# ECG_V3.net
KiCad netlist of a schematic drawn in EAGLE
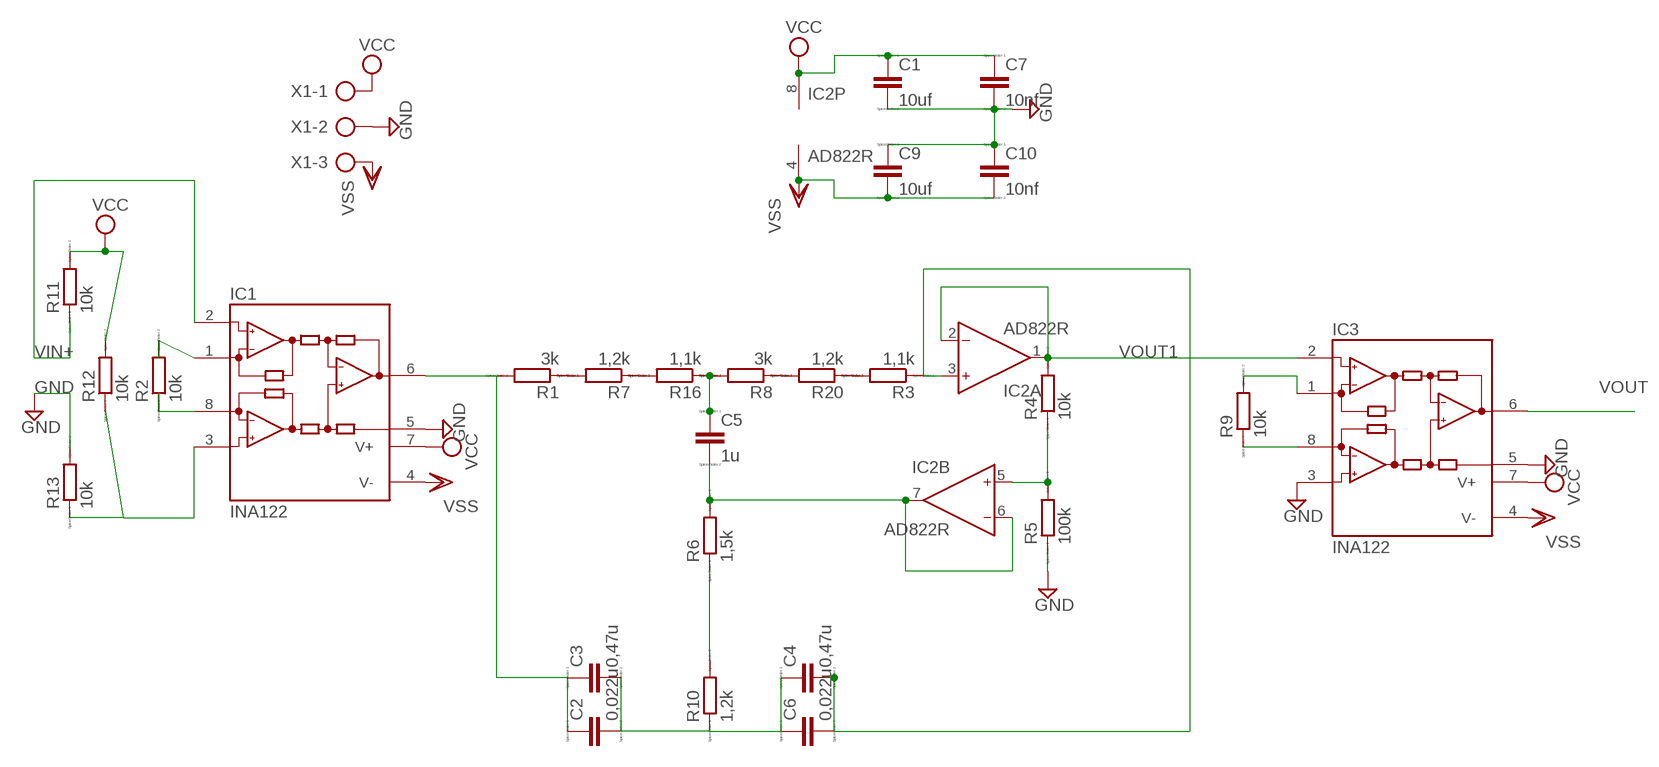
[diagram p0: schematic, sheet 1]

(export (version "E")
  (design (tool "Eeschema 10.0.6"))
  (components
    (comp (ref "C1")
      (value "10uf")
      (footprint "eagle-import:C0603")
      (libsource (lib "eagle-import") (part "CC0603"))
    )
    (comp (ref "C2")
      (value "0,022u")
      (footprint "eagle-import:C0603")
      (libsource (lib "eagle-import") (part "CC0603"))
    )
    (comp (ref "C3")
      (value "0,47u")
      (footprint "eagle-import:C0603")
      (libsource (lib "eagle-import") (part "CC0603"))
    )
    (comp (ref "C4")
      (value "0,47u")
      (footprint "eagle-import:C0603")
      (libsource (lib "eagle-import") (part "CC0603"))
    )
    (comp (ref "C5")
      (value "1u")
      (footprint "eagle-import:C0603")
      (libsource (lib "eagle-import") (part "CC0603"))
    )
    (comp (ref "C6")
      (value "0,022u")
      (footprint "eagle-import:C0603")
      (libsource (lib "eagle-import") (part "CC0603"))
    )
    (comp (ref "C7")
      (value "10nf")
      (footprint "eagle-import:C0603")
      (libsource (lib "eagle-import") (part "CC0603"))
    )
    (comp (ref "C9")
      (value "10uf")
      (footprint "eagle-import:C0603")
      (libsource (lib "eagle-import") (part "CC0603"))
    )
    (comp (ref "C10")
      (value "10nf")
      (footprint "eagle-import:C0603")
      (libsource (lib "eagle-import") (part "CC0603"))
    )
    (comp (ref "IC1")
      (value "INA122")
      (footprint "eagle-import:SO08")
      (fields (field (name "MF") "TEXAS INSTRUMENTS") (field (name "MPN") "INA118U"))
      (libsource (lib "eagle-import") (part "INA118U"))
    )
    (comp (ref "IC2")
      (value "AD822R")
      (footprint "eagle-import:SO8")
      (fields (field (name "MF") "ANALOG DEVICES") (field (name "MPN") "AD822BRZ"))
      (libsource (lib "eagle-import") (part "AD822R"))
    )
    (comp (ref "IC3")
      (value "INA122")
      (footprint "eagle-import:SO08")
      (fields (field (name "MF") "TEXAS INSTRUMENTS") (field (name "MPN") "INA118U"))
      (libsource (lib "eagle-import") (part "INA118U"))
    )
    (comp (ref "R1")
      (value "3k")
      (footprint "eagle-import:R0603")
      (libsource (lib "eagle-import") (part "RR0603"))
    )
    (comp (ref "R2")
      (value "10k")
      (footprint "eagle-import:R0603")
      (libsource (lib "eagle-import") (part "RR0603"))
    )
    (comp (ref "R3")
      (value "1,1k")
      (footprint "eagle-import:R0603")
      (libsource (lib "eagle-import") (part "RR0603"))
    )
    (comp (ref "R4")
      (value "10k")
      (footprint "eagle-import:R0603")
      (libsource (lib "eagle-import") (part "RR0603"))
    )
    (comp (ref "R5")
      (value "100k")
      (footprint "eagle-import:R0603")
      (libsource (lib "eagle-import") (part "RR0603"))
    )
    (comp (ref "R6")
      (value "1,5k")
      (footprint "eagle-import:R0603")
      (libsource (lib "eagle-import") (part "RR0603"))
    )
    (comp (ref "R7")
      (value "1,2k")
      (footprint "eagle-import:R0603")
      (libsource (lib "eagle-import") (part "RR0603"))
    )
    (comp (ref "R8")
      (value "3k")
      (footprint "eagle-import:R0603")
      (libsource (lib "eagle-import") (part "RR0603"))
    )
    (comp (ref "R9")
      (value "10k")
      (footprint "eagle-import:R0603")
      (libsource (lib "eagle-import") (part "RR0603"))
    )
    (comp (ref "R10")
      (value "1,2k")
      (footprint "eagle-import:R0603")
      (libsource (lib "eagle-import") (part "RR0603"))
    )
    (comp (ref "R11")
      (value "10k")
      (footprint "eagle-import:R0603")
      (libsource (lib "eagle-import") (part "RR0603"))
    )
    (comp (ref "R12")
      (value "10k")
      (footprint "eagle-import:R0603")
      (libsource (lib "eagle-import") (part "RR0603"))
    )
    (comp (ref "R13")
      (value "10k")
      (footprint "eagle-import:R0603")
      (libsource (lib "eagle-import") (part "RR0603"))
    )
    (comp (ref "R16")
      (value "1,1k")
      (footprint "eagle-import:R0603")
      (libsource (lib "eagle-import") (part "RR0603"))
    )
    (comp (ref "R20")
      (value "1,2k")
      (footprint "eagle-import:R0603")
      (libsource (lib "eagle-import") (part "RR0603"))
    )
    (comp (ref "X1")
      (value "AK300/3")
      (footprint "eagle-import:AK300_3")
      (libsource (lib "eagle-import") (part "AK300/3"))
    )
  )
  (nets
    (net (code "1") (name "/VIN+") (class "Default")
      (node (ref "IC1") (pin "2") (pinfunction "-IN_2") (pintype "input"))
      (node (ref "R11") (pin "1") (pinfunction "1_1") (pintype "passive"))
    )
    (net (code "2") (name "/VOUT") (class "Default")
      (node (ref "IC3") (pin "6") (pinfunction "OUT_6") (pintype "output"))
    )
    (net (code "3") (name "/VOUT1") (class "Default")
      (node (ref "IC2") (pin "1") (pinfunction "OUT_1") (pintype "output"))
      (node (ref "IC2") (pin "2") (pinfunction "IN-_2") (pintype "input"))
      (node (ref "IC3") (pin "2") (pinfunction "-IN_2") (pintype "input"))
      (node (ref "R4") (pin "2") (pinfunction "2_2") (pintype "passive"))
    )
    (net (code "4") (name "GND") (class "Default")
      (node (ref "C1") (pin "2") (pinfunction "2_2") (pintype "passive"))
      (node (ref "C10") (pin "1") (pinfunction "1_1") (pintype "passive"))
      (node (ref "C7") (pin "2") (pinfunction "2_2") (pintype "passive"))
      (node (ref "C9") (pin "1") (pinfunction "1_1") (pintype "passive"))
      (node (ref "IC1") (pin "5") (pinfunction "REF_5") (pintype "passive"))
      (node (ref "IC3") (pin "3") (pinfunction "+IN_3") (pintype "input"))
      (node (ref "IC3") (pin "5") (pinfunction "REF_5") (pintype "passive"))
      (node (ref "R13") (pin "2") (pinfunction "2_2") (pintype "passive"))
      (node (ref "R5") (pin "1") (pinfunction "1_1") (pintype "passive"))
      (node (ref "X1") (pin "2") (pinfunction "KL_2") (pintype "passive"))
    )
    (net (code "5") (name "Net-(C2-Pad2)") (class "Default")
      (node (ref "C2") (pin "2") (pinfunction "2_2") (pintype "passive"))
      (node (ref "C3") (pin "2") (pinfunction "2_2") (pintype "passive"))
      (node (ref "C4") (pin "1") (pinfunction "1_1") (pintype "passive"))
      (node (ref "C6") (pin "1") (pinfunction "1_1") (pintype "passive"))
      (node (ref "R10") (pin "1") (pinfunction "1_1") (pintype "passive"))
    )
    (net (code "6") (name "Net-(C5-Pad1)") (class "Default")
      (node (ref "C5") (pin "1") (pinfunction "1_1") (pintype "passive"))
      (node (ref "R16") (pin "1") (pinfunction "1_1") (pintype "passive"))
      (node (ref "R8") (pin "2") (pinfunction "2_2") (pintype "passive"))
    )
    (net (code "7") (name "Net-(IC1-+IN)") (class "Default")
      (node (ref "IC1") (pin "3") (pinfunction "+IN_3") (pintype "input"))
      (node (ref "R12") (pin "1") (pinfunction "1_1") (pintype "passive"))
      (node (ref "R13") (pin "1") (pinfunction "1_1") (pintype "passive"))
    )
    (net (code "8") (name "Net-(IC1-OUT)") (class "Default")
      (node (ref "C2") (pin "1") (pinfunction "1_1") (pintype "passive"))
      (node (ref "C3") (pin "1") (pinfunction "1_1") (pintype "passive"))
      (node (ref "IC1") (pin "6") (pinfunction "OUT_6") (pintype "output"))
      (node (ref "R1") (pin "2") (pinfunction "2_2") (pintype "passive"))
    )
    (net (code "9") (name "Net-(IC1-RG-Pad1)") (class "Default")
      (node (ref "IC1") (pin "1") (pinfunction "RG_1") (pintype "passive"))
      (node (ref "R2") (pin "2") (pinfunction "2_2") (pintype "passive"))
    )
    (net (code "10") (name "Net-(IC1-RG-Pad8)") (class "Default")
      (node (ref "IC1") (pin "8") (pinfunction "RG_8") (pintype "passive"))
      (node (ref "R2") (pin "1") (pinfunction "1_1") (pintype "passive"))
    )
    (net (code "11") (name "Net-(IC2A-IN+)") (class "Default")
      (node (ref "C4") (pin "2") (pinfunction "2_2") (pintype "passive"))
      (node (ref "C6") (pin "2") (pinfunction "2_2") (pintype "passive"))
      (node (ref "IC2") (pin "3") (pinfunction "IN+_3") (pintype "input"))
      (node (ref "R3") (pin "1") (pinfunction "1_1") (pintype "passive"))
    )
    (net (code "12") (name "Net-(IC2B-IN+)") (class "Default")
      (node (ref "IC2") (pin "5") (pinfunction "IN+_5") (pintype "input"))
      (node (ref "R4") (pin "1") (pinfunction "1_1") (pintype "passive"))
      (node (ref "R5") (pin "2") (pinfunction "2_2") (pintype "passive"))
    )
    (net (code "13") (name "Net-(IC2B-IN-)") (class "Default")
      (node (ref "C5") (pin "2") (pinfunction "2_2") (pintype "passive"))
      (node (ref "IC2") (pin "6") (pinfunction "IN-_6") (pintype "input"))
      (node (ref "IC2") (pin "7") (pinfunction "OUT_7") (pintype "output"))
      (node (ref "R6") (pin "2") (pinfunction "2_2") (pintype "passive"))
    )
    (net (code "14") (name "Net-(IC3-RG-Pad1)") (class "Default")
      (node (ref "IC3") (pin "1") (pinfunction "RG_1") (pintype "passive"))
      (node (ref "R9") (pin "2") (pinfunction "2_2") (pintype "passive"))
    )
    (net (code "15") (name "Net-(IC3-RG-Pad8)") (class "Default")
      (node (ref "IC3") (pin "8") (pinfunction "RG_8") (pintype "passive"))
      (node (ref "R9") (pin "1") (pinfunction "1_1") (pintype "passive"))
    )
    (net (code "16") (name "Net-(R1-Pad1)") (class "Default")
      (node (ref "R1") (pin "1") (pinfunction "1_1") (pintype "passive"))
      (node (ref "R7") (pin "2") (pinfunction "2_2") (pintype "passive"))
    )
    (net (code "17") (name "Net-(R10-Pad2)") (class "Default")
      (node (ref "R10") (pin "2") (pinfunction "2_2") (pintype "passive"))
      (node (ref "R6") (pin "1") (pinfunction "1_1") (pintype "passive"))
    )
    (net (code "18") (name "Net-(R16-Pad2)") (class "Default")
      (node (ref "R16") (pin "2") (pinfunction "2_2") (pintype "passive"))
      (node (ref "R7") (pin "1") (pinfunction "1_1") (pintype "passive"))
    )
    (net (code "19") (name "Net-(R20-Pad1)") (class "Default")
      (node (ref "R20") (pin "1") (pinfunction "1_1") (pintype "passive"))
      (node (ref "R3") (pin "2") (pinfunction "2_2") (pintype "passive"))
    )
    (net (code "20") (name "Net-(R20-Pad2)") (class "Default")
      (node (ref "R20") (pin "2") (pinfunction "2_2") (pintype "passive"))
      (node (ref "R8") (pin "1") (pinfunction "1_1") (pintype "passive"))
    )
    (net (code "21") (name "VCC") (class "Default")
      (node (ref "C1") (pin "1") (pinfunction "1_1") (pintype "passive"))
      (node (ref "C7") (pin "1") (pinfunction "1_1") (pintype "passive"))
      (node (ref "IC1") (pin "7") (pinfunction "V+_7") (pintype "power_in"))
      (node (ref "IC2") (pin "8") (pinfunction "V+_8") (pintype "power_in"))
      (node (ref "IC3") (pin "7") (pinfunction "V+_7") (pintype "power_in"))
      (node (ref "R11") (pin "2") (pinfunction "2_2") (pintype "passive"))
      (node (ref "R12") (pin "2") (pinfunction "2_2") (pintype "passive"))
      (node (ref "X1") (pin "1") (pinfunction "KL_1") (pintype "passive"))
    )
    (net (code "22") (name "VSS") (class "Default")
      (node (ref "C10") (pin "2") (pinfunction "2_2") (pintype "passive"))
      (node (ref "C9") (pin "2") (pinfunction "2_2") (pintype "passive"))
      (node (ref "IC1") (pin "4") (pinfunction "V-_4") (pintype "power_in"))
      (node (ref "IC2") (pin "4") (pinfunction "V-_4") (pintype "power_in"))
      (node (ref "IC3") (pin "4") (pinfunction "V-_4") (pintype "power_in"))
      (node (ref "X1") (pin "3") (pinfunction "KL_3") (pintype "passive"))
    )
  )
)
